# MCU.net
KiCad netlist of a schematic drawn in Altium Designer
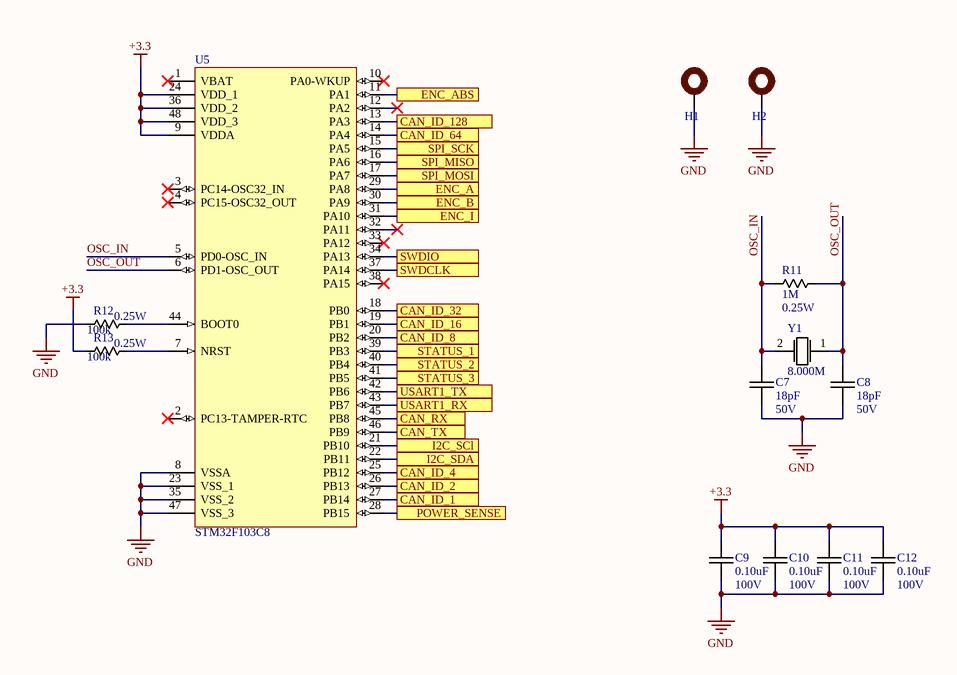
[diagram p0: MCU.SchDoc]

(export (version "E")
  (design (tool "Eeschema 10.0.6"))
  (components
    (comp (ref "C7")
      (value "cap_single_np")
      (footprint "chip_0603")
      (description "CAP, 18pF, ±1%, 50V, C0G, 0603")
      (fields
        (field (name "TOLERANCE") "±1%")
        (field (name "CAPACITANCE") "18pF")
        (field (name "VOLTAGE RATING") "50V")
        (field (name "PART NUMBER") "CAP-00417")
      )
      (libsource (lib "Capacitors") (part "cap_single_np"))
    )
    (comp (ref "C8")
      (value "cap_single_np")
      (footprint "chip_0603")
      (description "CAP, 18pF, ±1%, 50V, C0G, 0603")
      (fields
        (field (name "TOLERANCE") "±1%")
        (field (name "CAPACITANCE") "18pF")
        (field (name "VOLTAGE RATING") "50V")
        (field (name "PART NUMBER") "CAP-00417")
      )
      (libsource (lib "Capacitors") (part "cap_single_np"))
    )
    (comp (ref "C9")
      (value "cap_single_np")
      (footprint "chip_0805")
      (description "CAP, 0.10uF, 10%, 100V, X7R, 0805")
      (fields
        (field (name "TOLERANCE") "10%")
        (field (name "CAPACITANCE") "0.10uF")
        (field (name "VOLTAGE RATING") "100V")
        (field (name "PART NUMBER") "CAP-00073")
      )
      (libsource (lib "Capacitors") (part "cap_single_np"))
    )
    (comp (ref "C10")
      (value "cap_single_np")
      (footprint "chip_0805")
      (description "CAP, 0.10uF, 10%, 100V, X7R, 0805")
      (fields
        (field (name "TOLERANCE") "10%")
        (field (name "CAPACITANCE") "0.10uF")
        (field (name "VOLTAGE RATING") "100V")
        (field (name "PART NUMBER") "CAP-00073")
      )
      (libsource (lib "Capacitors") (part "cap_single_np"))
    )
    (comp (ref "C11")
      (value "cap_single_np")
      (footprint "chip_0805")
      (description "CAP, 0.10uF, 10%, 100V, X7R, 0805")
      (fields
        (field (name "TOLERANCE") "10%")
        (field (name "CAPACITANCE") "0.10uF")
        (field (name "VOLTAGE RATING") "100V")
        (field (name "PART NUMBER") "CAP-00073")
      )
      (libsource (lib "Capacitors") (part "cap_single_np"))
    )
    (comp (ref "C12")
      (value "cap_single_np")
      (footprint "chip_0805")
      (description "CAP, 0.10uF, 10%, 100V, X7R, 0805")
      (fields
        (field (name "TOLERANCE") "10%")
        (field (name "CAPACITANCE") "0.10uF")
        (field (name "VOLTAGE RATING") "100V")
        (field (name "PART NUMBER") "CAP-00073")
      )
      (libsource (lib "Capacitors") (part "cap_single_np"))
    )
    (comp (ref "H1")
      (value "mounting_hole_0")
      (footprint "#8-32_SOCKET_HEAD")
      (description "#8-32 Mounting Hole for Socket Head Cap Screw")
      (fields (field (name "PART NUMBER") "MISC-00027"))
      (libsource (lib "Misc") (part "mounting_hole_0"))
    )
    (comp (ref "H2")
      (value "mounting_hole_0")
      (footprint "#8-32_SOCKET_HEAD")
      (description "#8-32 Mounting Hole for Socket Head Cap Screw")
      (fields (field (name "PART NUMBER") "MISC-00027"))
      (libsource (lib "Misc") (part "mounting_hole_0"))
    )
    (comp (ref "R11")
      (value "res_single")
      (footprint "chip_0603")
      (description "RES SMD 1M OHM 1% 1/4W 0603")
      (fields
        (field (name "TOLERANCE") "1%")
        (field (name "RESISTANCE") "1M")
        (field (name "POWER RATING") "0.25W")
        (field (name "PART NUMBER") "RES-00362")
      )
      (libsource (lib "Resistors") (part "res_single"))
    )
    (comp (ref "R12")
      (value "res_single")
      (footprint "chip_0603")
      (description "RES SMD 100K OHM 1% 1/4W 0603")
      (fields
        (field (name "TOLERANCE") "1%")
        (field (name "RESISTANCE") "100k")
        (field (name "POWER RATING") "0.25W")
        (field (name "PART NUMBER") "RES-00301")
      )
      (libsource (lib "Resistors") (part "res_single"))
    )
    (comp (ref "R13")
      (value "res_single")
      (footprint "chip_0603")
      (description "RES SMD 100K OHM 1% 1/4W 0603")
      (fields
        (field (name "TOLERANCE") "1%")
        (field (name "RESISTANCE") "100k")
        (field (name "POWER RATING") "0.25W")
        (field (name "PART NUMBER") "RES-00301")
      )
      (libsource (lib "Resistors") (part "res_single"))
    )
    (comp (ref "U5")
      (value "STM32F103C8")
      (footprint "LQFP48_0")
      (description "STM32 M3, LQFP-48")
      (fields (field (name "PART NUMBER") "UCTRL-00008") (field (name "MANUFACTURER") "ST"))
      (libsource (lib "Microcontrollers") (part "STM32F103C8"))
    )
    (comp (ref "Y1")
      (value "osc_xtal_2p_0")
      (footprint "ABLS_AT49_OSC")
      (description "XTAL, 8MHz, 18pF, 20ppm")
      (fields
        (field (name "TOLERANCE") "20ppm")
        (field (name "FREQUENCY") "8.000M")
        (field (name "PART NUMBER") "OSC-00002")
      )
      (libsource (lib "Oscillators") (part "osc_xtal_2p_0"))
    )
  )
  (nets
    (net (code "1") (name "+3.3") (class "Default")
      (node (ref "C10") (pin "1") (pinfunction "1_1") (pintype "passive"))
      (node (ref "C11") (pin "1") (pinfunction "1_1") (pintype "passive"))
      (node (ref "C12") (pin "1") (pinfunction "1_1") (pintype "passive"))
      (node (ref "C9") (pin "1") (pinfunction "1_1") (pintype "passive"))
      (node (ref "R13") (pin "2") (pinfunction "2_2") (pintype "passive"))
      (node (ref "U5") (pin "24") (pinfunction "VDD_1_24") (pintype "power_in"))
      (node (ref "U5") (pin "36") (pinfunction "VDD_2_36") (pintype "power_in"))
      (node (ref "U5") (pin "48") (pinfunction "VDD_3_48") (pintype "power_in"))
      (node (ref "U5") (pin "9") (pinfunction "VDDA_9") (pintype "power_in"))
    )
    (net (code "2") (name "/CAN_ID_1") (class "Default")
      (node (ref "U5") (pin "27") (pinfunction "PB14_27") (pintype "bidirectional"))
    )
    (net (code "3") (name "/CAN_ID_2") (class "Default")
      (node (ref "U5") (pin "26") (pinfunction "PB13_26") (pintype "bidirectional"))
    )
    (net (code "4") (name "/CAN_ID_4") (class "Default")
      (node (ref "U5") (pin "25") (pinfunction "PB12_25") (pintype "bidirectional"))
    )
    (net (code "5") (name "/CAN_ID_8") (class "Default")
      (node (ref "U5") (pin "20") (pinfunction "PB2_20") (pintype "bidirectional"))
    )
    (net (code "6") (name "/CAN_ID_16") (class "Default")
      (node (ref "U5") (pin "19") (pinfunction "PB1_19") (pintype "bidirectional"))
    )
    (net (code "7") (name "/CAN_ID_32") (class "Default")
      (node (ref "U5") (pin "18") (pinfunction "PB0_18") (pintype "bidirectional"))
    )
    (net (code "8") (name "/CAN_ID_64") (class "Default")
      (node (ref "U5") (pin "14") (pinfunction "PA4_14") (pintype "bidirectional"))
    )
    (net (code "9") (name "/CAN_ID_128") (class "Default")
      (node (ref "U5") (pin "13") (pinfunction "PA3_13") (pintype "bidirectional"))
    )
    (net (code "10") (name "/CAN_RX") (class "Default")
      (node (ref "U5") (pin "45") (pinfunction "PB8_45") (pintype "bidirectional"))
    )
    (net (code "11") (name "/CAN_TX") (class "Default")
      (node (ref "U5") (pin "46") (pinfunction "PB9_46") (pintype "bidirectional"))
    )
    (net (code "12") (name "/ENC_A") (class "Default")
      (node (ref "U5") (pin "29") (pinfunction "PA8_29") (pintype "bidirectional"))
    )
    (net (code "13") (name "/ENC_ABS") (class "Default")
      (node (ref "U5") (pin "11") (pinfunction "PA1_11") (pintype "bidirectional"))
    )
    (net (code "14") (name "/ENC_B") (class "Default")
      (node (ref "U5") (pin "30") (pinfunction "PA9_30") (pintype "bidirectional"))
    )
    (net (code "15") (name "/ENC_I") (class "Default")
      (node (ref "U5") (pin "31") (pinfunction "PA10_31") (pintype "bidirectional"))
    )
    (net (code "16") (name "/I2C_SCl") (class "Default")
      (node (ref "U5") (pin "21") (pinfunction "PB10_21") (pintype "bidirectional"))
    )
    (net (code "17") (name "/I2C_SDA") (class "Default")
      (node (ref "U5") (pin "22") (pinfunction "PB11_22") (pintype "bidirectional"))
    )
    (net (code "18") (name "/OSC_IN") (class "Default")
      (node (ref "C7") (pin "1") (pinfunction "1_1") (pintype "passive"))
      (node (ref "R11") (pin "1") (pinfunction "1_1") (pintype "passive"))
      (node (ref "U5") (pin "5") (pinfunction "PD0-OSC_IN_5") (pintype "bidirectional"))
      (node (ref "Y1") (pin "2") (pinfunction "20_2") (pintype "passive"))
    )
    (net (code "19") (name "/OSC_OUT") (class "Default")
      (node (ref "C8") (pin "1") (pinfunction "1_1") (pintype "passive"))
      (node (ref "R11") (pin "2") (pinfunction "2_2") (pintype "passive"))
      (node (ref "U5") (pin "6") (pinfunction "PD1-OSC_OUT_6") (pintype "bidirectional"))
      (node (ref "Y1") (pin "1") (pinfunction "20_1") (pintype "passive"))
    )
    (net (code "20") (name "/POWER_SENSE") (class "Default")
      (node (ref "U5") (pin "28") (pinfunction "PB15_28") (pintype "bidirectional"))
    )
    (net (code "21") (name "/SPI_MISO") (class "Default")
      (node (ref "U5") (pin "16") (pinfunction "PA6_16") (pintype "bidirectional"))
    )
    (net (code "22") (name "/SPI_MOSI") (class "Default")
      (node (ref "U5") (pin "17") (pinfunction "PA7_17") (pintype "bidirectional"))
    )
    (net (code "23") (name "/SPI_SCK") (class "Default")
      (node (ref "U5") (pin "15") (pinfunction "PA5_15") (pintype "bidirectional"))
    )
    (net (code "24") (name "/STATUS_1") (class "Default")
      (node (ref "U5") (pin "39") (pinfunction "PB3_39") (pintype "bidirectional"))
    )
    (net (code "25") (name "/STATUS_2") (class "Default")
      (node (ref "U5") (pin "40") (pinfunction "PB4_40") (pintype "bidirectional"))
    )
    (net (code "26") (name "/STATUS_3") (class "Default")
      (node (ref "U5") (pin "41") (pinfunction "PB5_41") (pintype "bidirectional"))
    )
    (net (code "27") (name "/SWDCLK") (class "Default")
      (node (ref "U5") (pin "37") (pinfunction "PA14_37") (pintype "bidirectional"))
    )
    (net (code "28") (name "/SWDIO") (class "Default")
      (node (ref "U5") (pin "34") (pinfunction "PA13_34") (pintype "bidirectional"))
    )
    (net (code "29") (name "/USART1_RX") (class "Default")
      (node (ref "U5") (pin "43") (pinfunction "PB7_43") (pintype "bidirectional"))
    )
    (net (code "30") (name "/USART1_TX") (class "Default")
      (node (ref "U5") (pin "42") (pinfunction "PB6_42") (pintype "bidirectional"))
    )
    (net (code "31") (name "GND") (class "Default")
      (node (ref "C10") (pin "2") (pinfunction "2_2") (pintype "passive"))
      (node (ref "C11") (pin "2") (pinfunction "2_2") (pintype "passive"))
      (node (ref "C12") (pin "2") (pinfunction "2_2") (pintype "passive"))
      (node (ref "C7") (pin "2") (pinfunction "2_2") (pintype "passive"))
      (node (ref "C8") (pin "2") (pinfunction "2_2") (pintype "passive"))
      (node (ref "C9") (pin "2") (pinfunction "2_2") (pintype "passive"))
      (node (ref "H1") (pin "0") (pinfunction "A_0") (pintype "passive"))
      (node (ref "H2") (pin "0") (pinfunction "A_0") (pintype "passive"))
      (node (ref "R12") (pin "2") (pinfunction "2_2") (pintype "passive"))
      (node (ref "U5") (pin "23") (pinfunction "VSS_1_23") (pintype "power_in"))
      (node (ref "U5") (pin "35") (pinfunction "VSS_2_35") (pintype "power_in"))
      (node (ref "U5") (pin "47") (pinfunction "VSS_3_47") (pintype "power_in"))
      (node (ref "U5") (pin "8") (pinfunction "VSSA_8") (pintype "power_in"))
    )
    (net (code "32") (name "Net-(U5-BOOT0)") (class "Default")
      (node (ref "R12") (pin "1") (pinfunction "1_1") (pintype "passive"))
      (node (ref "U5") (pin "44") (pinfunction "BOOT0_44") (pintype "input"))
    )
    (net (code "33") (name "Net-(U5-NRST)") (class "Default")
      (node (ref "R13") (pin "1") (pinfunction "1_1") (pintype "passive"))
      (node (ref "U5") (pin "7") (pinfunction "NRST_7") (pintype "input"))
    )
    (net (code "34") (name "unconnected-(U5-PA0-WKUP-Pad10)") (class "Default")
      (node (ref "U5") (pin "10") (pinfunction "PA0-WKUP_10") (pintype "bidirectional+no_connect"))
    )
    (net (code "35") (name "unconnected-(U5-PA2-Pad12)") (class "Default")
      (node (ref "U5") (pin "12") (pinfunction "PA2_12") (pintype "bidirectional+no_connect"))
    )
    (net (code "36") (name "unconnected-(U5-PA11-Pad32)") (class "Default")
      (node (ref "U5") (pin "32") (pinfunction "PA11_32") (pintype "bidirectional+no_connect"))
    )
    (net (code "37") (name "unconnected-(U5-PA12-Pad33)") (class "Default")
      (node (ref "U5") (pin "33") (pinfunction "PA12_33") (pintype "bidirectional+no_connect"))
    )
    (net (code "38") (name "unconnected-(U5-PA15-Pad38)") (class "Default")
      (node (ref "U5") (pin "38") (pinfunction "PA15_38") (pintype "bidirectional+no_connect"))
    )
    (net (code "39") (name "unconnected-(U5-PC13-TAMPER-RTC-Pad2)") (class "Default")
      (node (ref "U5") (pin "2") (pinfunction "PC13-TAMPER-RTC_2") (pintype "bidirectional+no_connect"))
    )
    (net (code "40") (name "unconnected-(U5-PC14-OSC32_IN-Pad3)") (class "Default")
      (node (ref "U5") (pin "3") (pinfunction "PC14-OSC32_IN_3") (pintype "bidirectional+no_connect"))
    )
    (net (code "41") (name "unconnected-(U5-PC15-OSC32_OUT-Pad4)") (class "Default")
      (node (ref "U5") (pin "4") (pinfunction "PC15-OSC32_OUT_4") (pintype "bidirectional+no_connect"))
    )
    (net (code "42") (name "unconnected-(U5-VBAT-Pad1)") (class "Default")
      (node (ref "U5") (pin "1") (pinfunction "VBAT_1") (pintype "passive+no_connect"))
    )
  )
)
